# Power_Supply_Slow_Start.net
KiCad netlist of a schematic drawn in EAGLE
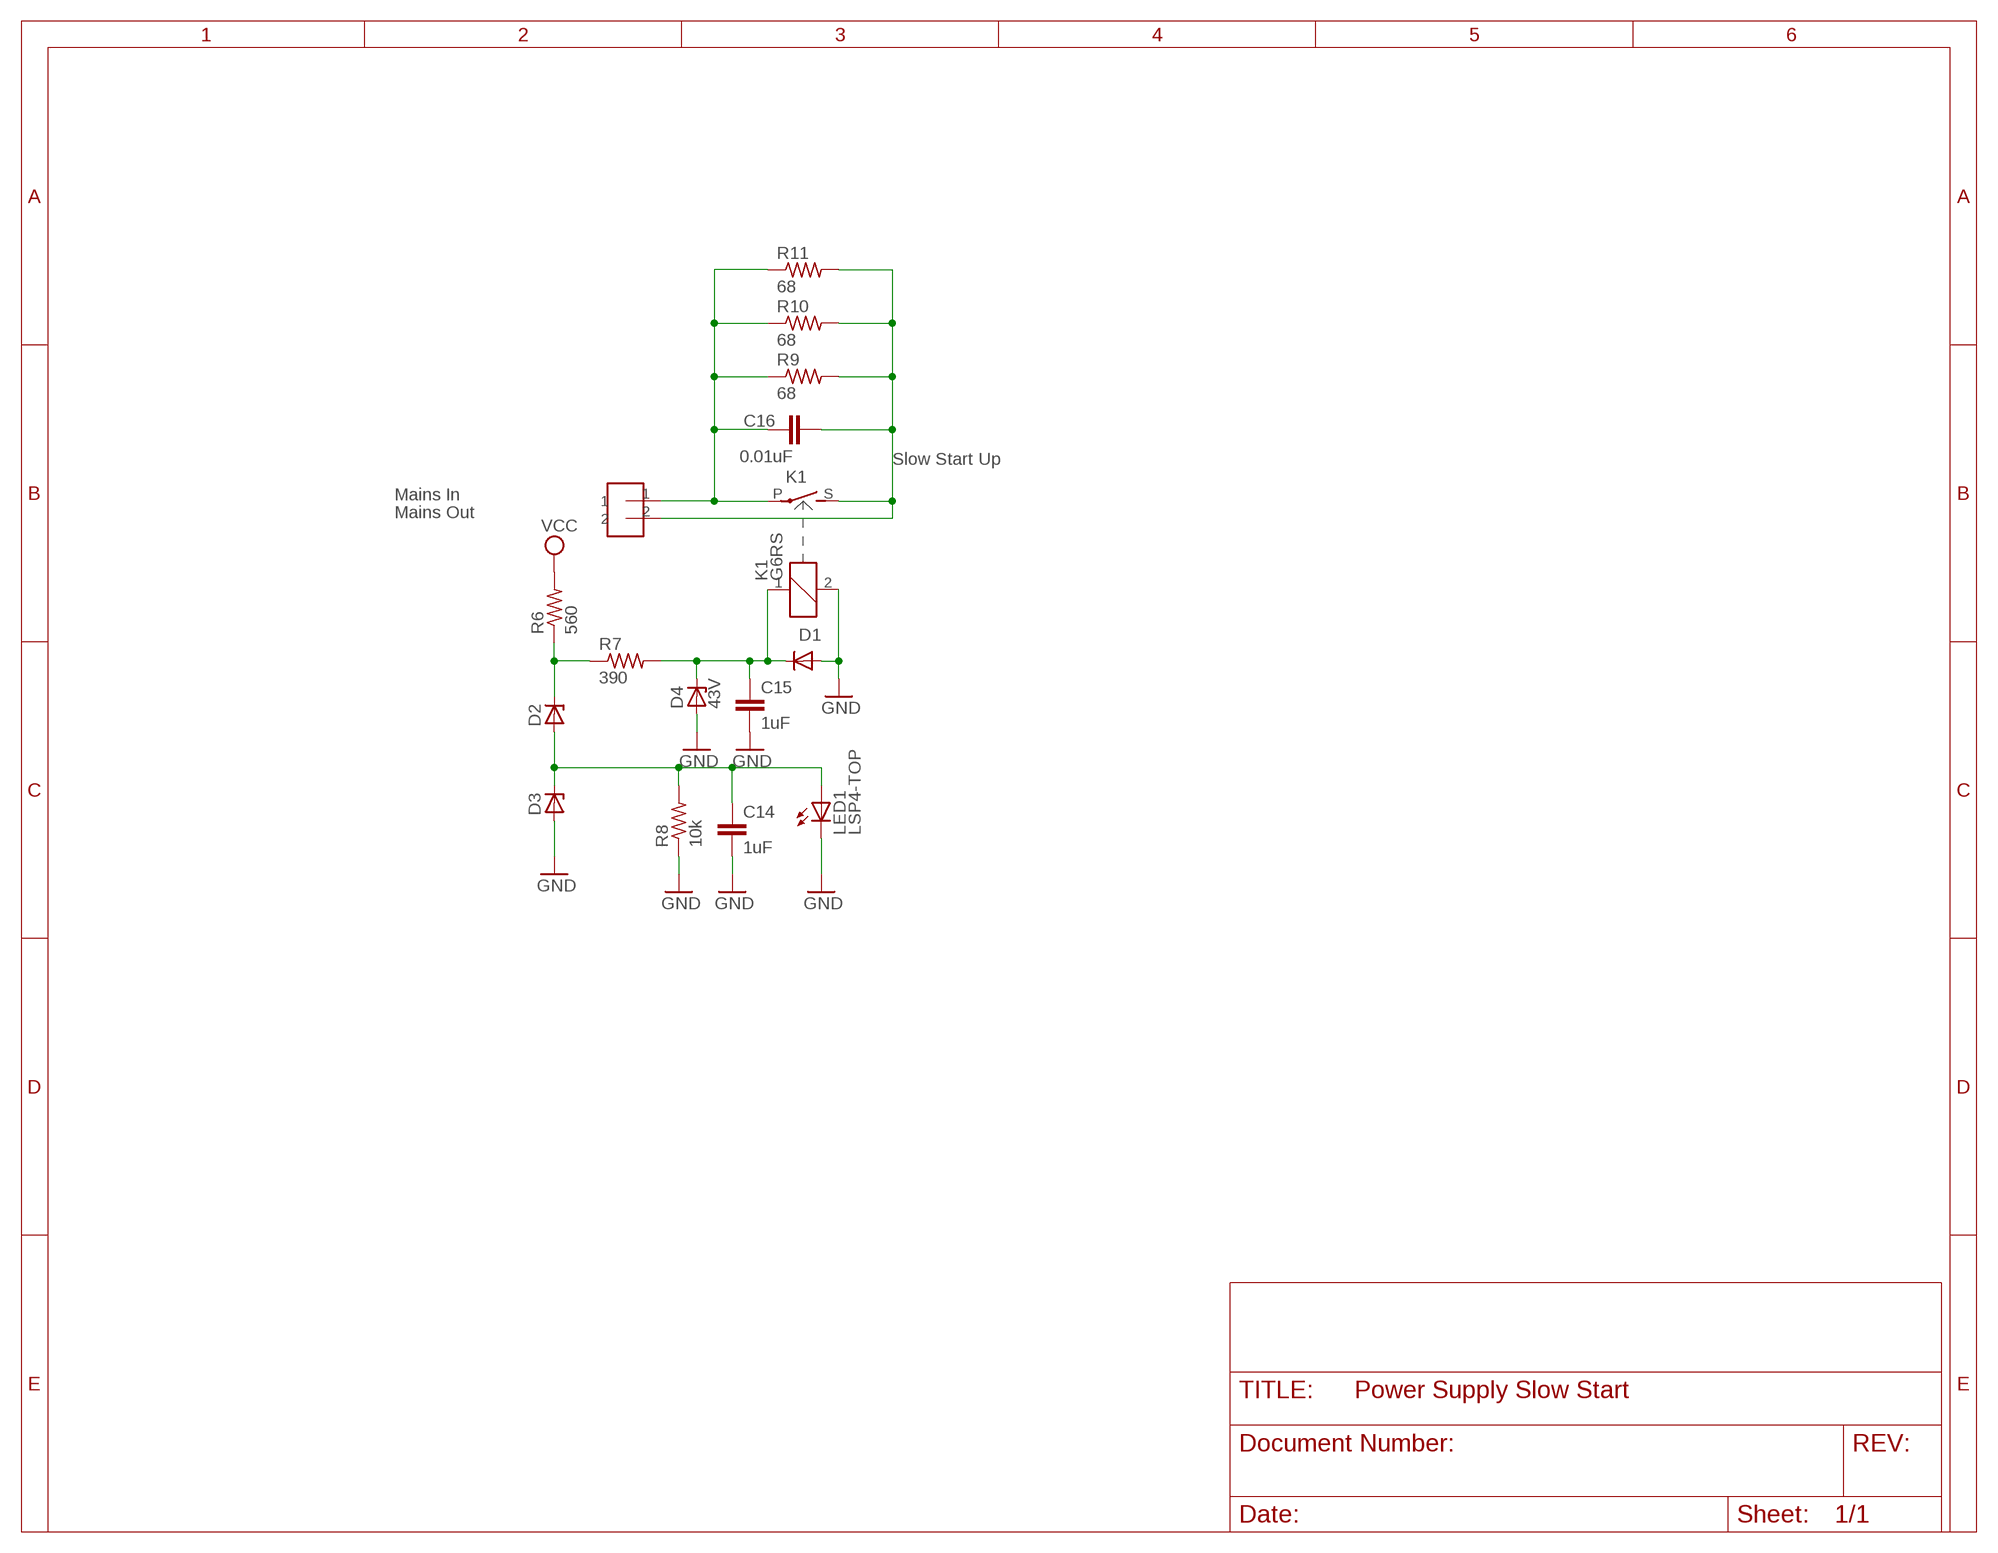
[diagram p0: schematic, sheet 1]

(export (version "E")
  (design (tool "Eeschema 10.0.6"))
  (components
    (comp (ref "C14")
      (value "1uF")
      (footprint "eagle-import:C025-060X050")
      (libsource (lib "eagle-import") (part "C-EU025-060X050"))
    )
    (comp (ref "C15")
      (value "1uF")
      (footprint "eagle-import:C025-060X050")
      (libsource (lib "eagle-import") (part "C-EU025-060X050"))
    )
    (comp (ref "C16")
      (value "0.01uF")
      (footprint "eagle-import:C025-060X050")
      (libsource (lib "eagle-import") (part "C-EU025-060X050"))
    )
    (comp (ref "D1")
      (value "1N4004")
      (footprint "eagle-import:DO41-10")
      (libsource (lib "eagle-import") (part "1N4004"))
    )
    (comp (ref "D2")
      (value "ZENER-DIODEDO34-7")
      (footprint "eagle-import:DO34Z7")
      (libsource (lib "eagle-import") (part "ZENER-DIODEDO34-7"))
    )
    (comp (ref "D3")
      (value "ZENER-DIODEDO34-7")
      (footprint "eagle-import:DO34Z7")
      (libsource (lib "eagle-import") (part "ZENER-DIODEDO34-7"))
    )
    (comp (ref "D4")
      (value "43V")
      (footprint "eagle-import:DO34Z7")
      (libsource (lib "eagle-import") (part "ZENER-DIODEDO34-7"))
    )
    (comp (ref "K1")
      (value "G6RS")
      (footprint "eagle-import:G6RS")
      (libsource (lib "eagle-import") (part "G6RS"))
    )
    (comp (ref "LED1")
      (value "LSP4-TOP")
      (footprint "eagle-import:P47F-TOP")
      (libsource (lib "eagle-import") (part "P4-TOPLS"))
    )
    (comp (ref "R6")
      (value "560")
      (footprint "eagle-import:0617_22")
      (libsource (lib "eagle-import") (part "R-US_0617/22"))
    )
    (comp (ref "R7")
      (value "390")
      (footprint "eagle-import:0617_22")
      (libsource (lib "eagle-import") (part "R-US_0617/22"))
    )
    (comp (ref "R8")
      (value "10k")
      (footprint "eagle-import:0617_22")
      (libsource (lib "eagle-import") (part "R-US_0617/22"))
    )
    (comp (ref "R9")
      (value "68")
      (footprint "eagle-import:0617_22")
      (libsource (lib "eagle-import") (part "R-US_0617/22"))
    )
    (comp (ref "R10")
      (value "68")
      (footprint "eagle-import:0617_22")
      (libsource (lib "eagle-import") (part "R-US_0617/22"))
    )
    (comp (ref "R11")
      (value "68")
      (footprint "eagle-import:0617_22")
      (libsource (lib "eagle-import") (part "R-US_0617/22"))
    )
    (comp (ref "U$4")
      (value "1X2HEADER_100MIL")
      (footprint "eagle-import:1X2_100MIL")
      (libsource (lib "eagle-import") (part "1X2HEADER_100MIL"))
    )
  )
  (nets
    (net (code "1") (name "GND") (class "Default")
      (node (ref "C14") (pin "2") (pinfunction "2_2") (pintype "passive"))
      (node (ref "C15") (pin "2") (pinfunction "2_2") (pintype "passive"))
      (node (ref "D1") (pin "A") (pinfunction "A_A") (pintype "passive"))
      (node (ref "D3") (pin "A") (pinfunction "A_A") (pintype "passive"))
      (node (ref "D4") (pin "A") (pinfunction "A_A") (pintype "passive"))
      (node (ref "K1") (pin "2") (pinfunction "2_2") (pintype "passive"))
      (node (ref "LED1") (pin "C") (pinfunction "C_C") (pintype "passive"))
      (node (ref "R8") (pin "1") (pinfunction "1_1") (pintype "passive"))
    )
    (net (code "2") (name "Net-(C14-Pad1)") (class "Default")
      (node (ref "C14") (pin "1") (pinfunction "1_1") (pintype "passive"))
      (node (ref "D2") (pin "A") (pinfunction "A_A") (pintype "passive"))
      (node (ref "D3") (pin "C") (pinfunction "C_C") (pintype "passive"))
      (node (ref "LED1") (pin "A") (pinfunction "A_A") (pintype "passive"))
      (node (ref "R8") (pin "2") (pinfunction "2_2") (pintype "passive"))
    )
    (net (code "3") (name "Net-(C15-Pad1)") (class "Default")
      (node (ref "C15") (pin "1") (pinfunction "1_1") (pintype "passive"))
      (node (ref "D1") (pin "C") (pinfunction "C_C") (pintype "passive"))
      (node (ref "D4") (pin "C") (pinfunction "C_C") (pintype "passive"))
      (node (ref "K1") (pin "1") (pinfunction "1_1") (pintype "passive"))
      (node (ref "R7") (pin "2") (pinfunction "2_2") (pintype "passive"))
    )
    (net (code "4") (name "Net-(C16-Pad1)") (class "Default")
      (node (ref "C16") (pin "1") (pinfunction "1_1") (pintype "passive"))
      (node (ref "K1") (pin "P") (pinfunction "P_P") (pintype "passive"))
      (node (ref "R10") (pin "1") (pinfunction "1_1") (pintype "passive"))
      (node (ref "R11") (pin "1") (pinfunction "1_1") (pintype "passive"))
      (node (ref "R9") (pin "1") (pinfunction "1_1") (pintype "passive"))
      (node (ref "U$4") (pin "1") (pinfunction "1_1") (pintype "bidirectional"))
    )
    (net (code "5") (name "Net-(C16-Pad2)") (class "Default")
      (node (ref "C16") (pin "2") (pinfunction "2_2") (pintype "passive"))
      (node (ref "K1") (pin "S") (pinfunction "S_S") (pintype "passive"))
      (node (ref "R10") (pin "2") (pinfunction "2_2") (pintype "passive"))
      (node (ref "R11") (pin "2") (pinfunction "2_2") (pintype "passive"))
      (node (ref "R9") (pin "2") (pinfunction "2_2") (pintype "passive"))
      (node (ref "U$4") (pin "2") (pinfunction "2_2") (pintype "bidirectional"))
    )
    (net (code "6") (name "Net-(D2-PadC)") (class "Default")
      (node (ref "D2") (pin "C") (pinfunction "C_C") (pintype "passive"))
      (node (ref "R6") (pin "1") (pinfunction "1_1") (pintype "passive"))
      (node (ref "R7") (pin "1") (pinfunction "1_1") (pintype "passive"))
    )
    (net (code "7") (name "VCC") (class "Default")
      (node (ref "R6") (pin "2") (pinfunction "2_2") (pintype "passive"))
    )
  )
)
